# open_cw_keyer_mk2_v30.net
KiCad netlist of a schematic drawn in EAGLE
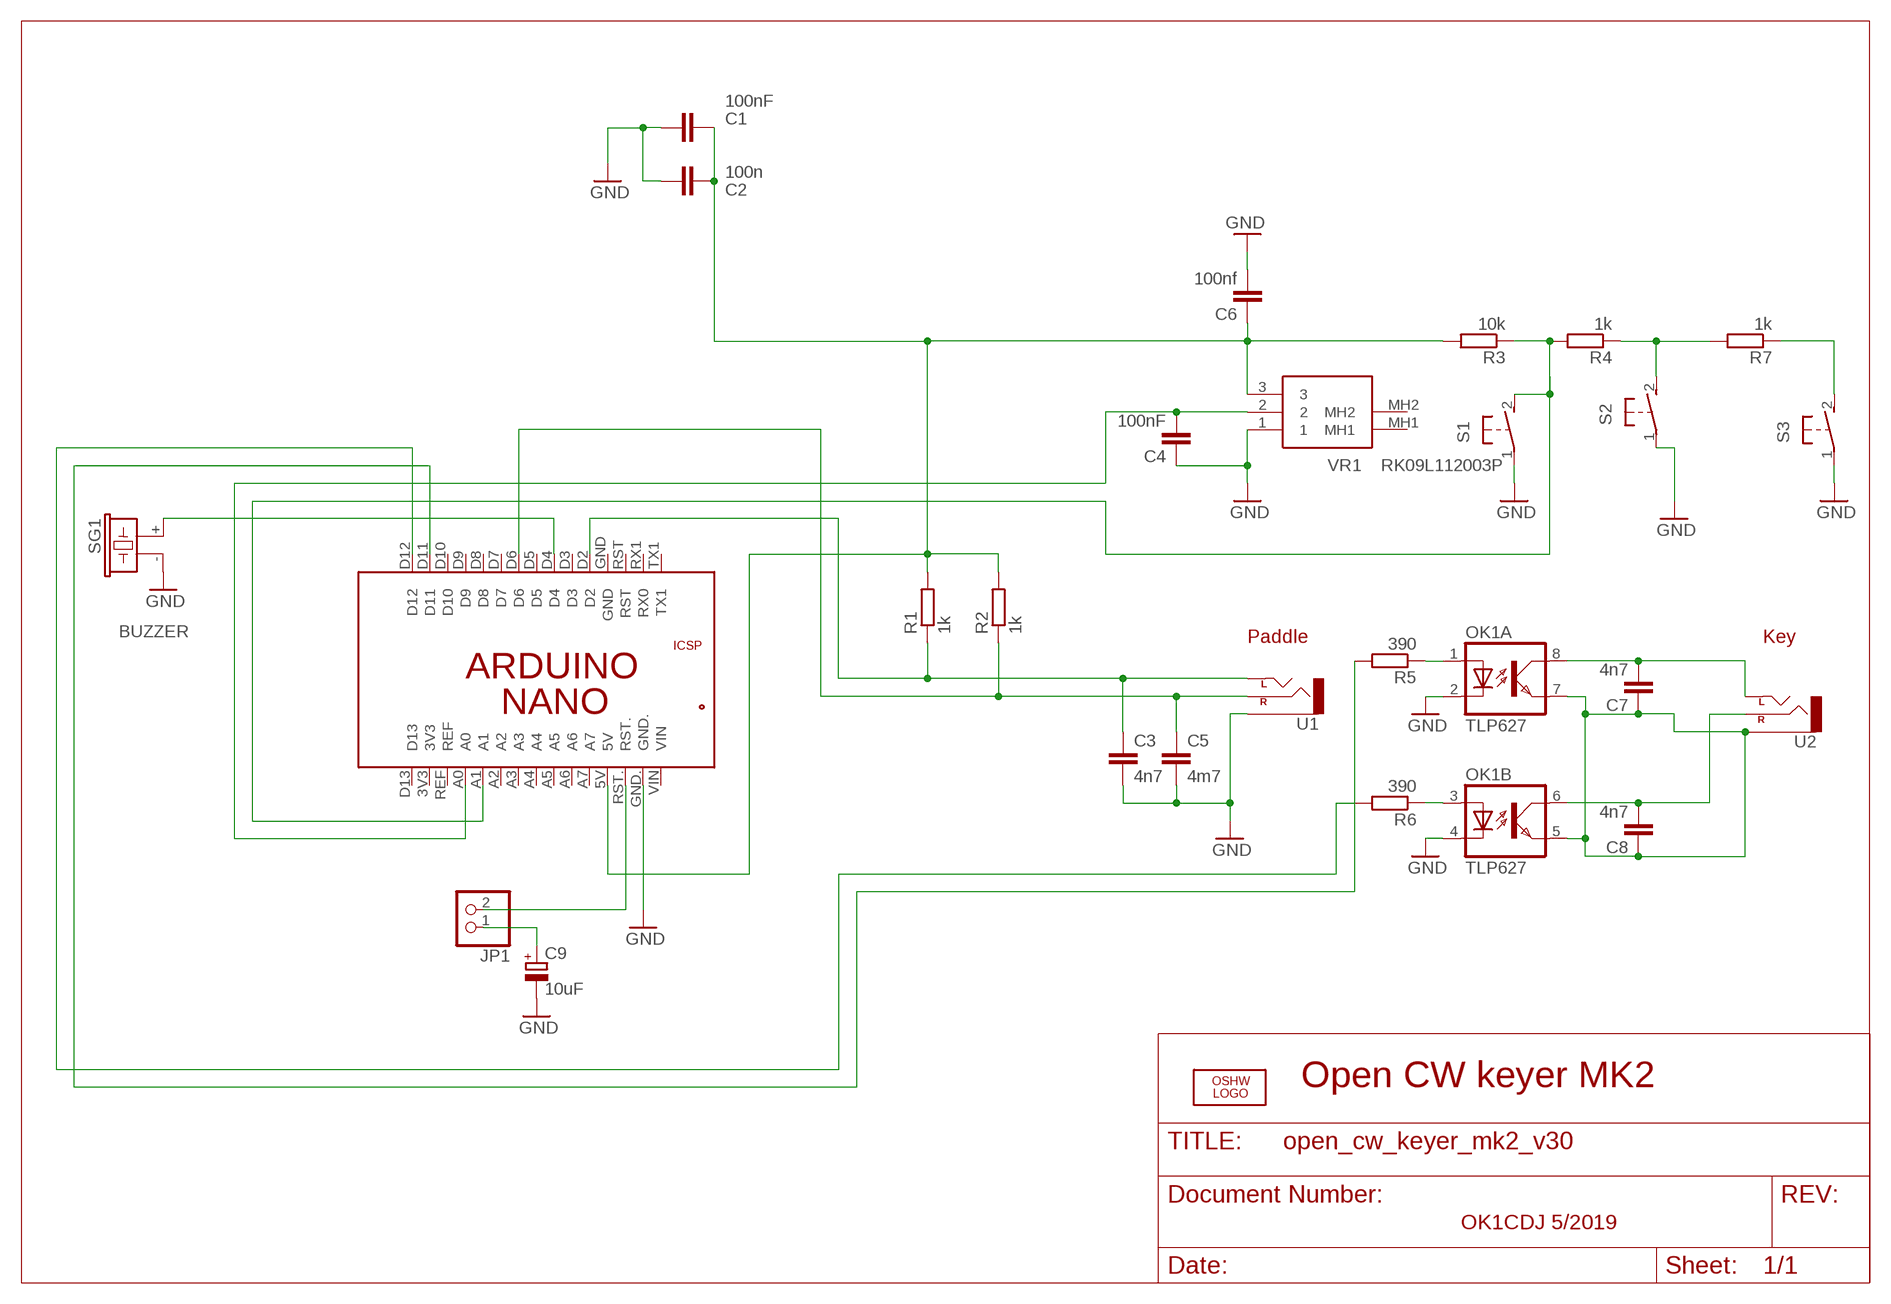
[diagram p0: schematic, sheet 1]

(export (version "E")
  (design (tool "Eeschema 10.0.6"))
  (components
    (comp (ref "C1")
      (value "100nF")
      (footprint "eagle-import:C0805")
      (libsource (lib "eagle-import") (part "C-EUC0805"))
    )
    (comp (ref "C2")
      (value "100n")
      (footprint "eagle-import:C0805")
      (libsource (lib "eagle-import") (part "C-EUC0805"))
    )
    (comp (ref "C3")
      (value "4n7")
      (footprint "eagle-import:C0805")
      (libsource (lib "eagle-import") (part "C-EUC0805"))
    )
    (comp (ref "C4")
      (value "100nF")
      (footprint "eagle-import:C0805")
      (libsource (lib "eagle-import") (part "C-EUC0805"))
    )
    (comp (ref "C5")
      (value "4m7")
      (footprint "eagle-import:C0805")
      (libsource (lib "eagle-import") (part "C-EUC0805"))
    )
    (comp (ref "C6")
      (value "100nf")
      (footprint "eagle-import:C0805")
      (libsource (lib "eagle-import") (part "C-EUC0805"))
    )
    (comp (ref "C7")
      (value "4n7")
      (footprint "eagle-import:C0805K")
      (libsource (lib "eagle-import") (part "C-EUC0805K"))
    )
    (comp (ref "C8")
      (value "4n7")
      (footprint "eagle-import:C0805K")
      (libsource (lib "eagle-import") (part "C-EUC0805K"))
    )
    (comp (ref "C9")
      (value "10uF")
      (footprint "eagle-import:B_3528-21R")
      (libsource (lib "eagle-import") (part "CPOL-EUB/3528-21R"))
    )
    (comp (ref "JP1")
      (value "PINHD-1X2/90")
      (footprint "eagle-import:1X02_90")
      (libsource (lib "eagle-import") (part "PINHD-1X2/90"))
    )
    (comp (ref "LOGO1")
      (value "OSHW_LOGO_FILLX0150-NT")
      (footprint "eagle-import:OSHW_FILLX150_NOTEXT")
      (libsource (lib "eagle-import") (part "OSHW_LOGO_FILLX0150-NT"))
    )
    (comp (ref "OK1")
      (value "TLP627")
      (footprint "eagle-import:DIL08")
      (fields (field (name "MF") "VISHAY/TELEFUNKEN") (field (name "MPN") "ILD621"))
      (libsource (lib "eagle-import") (part "ILD621"))
    )
    (comp (ref "PCB1")
      (value "ARDUINO_NANO")
      (footprint "eagle-import:ARDUINO_NANO")
      (libsource (lib "eagle-import") (part "ARDUINO_NANO"))
    )
    (comp (ref "R1")
      (value "1k")
      (footprint "eagle-import:M0805")
      (libsource (lib "eagle-import") (part "R-EU_M0805"))
    )
    (comp (ref "R2")
      (value "1k")
      (footprint "eagle-import:M0805")
      (libsource (lib "eagle-import") (part "R-EU_M0805"))
    )
    (comp (ref "R3")
      (value "10k")
      (footprint "eagle-import:M0805")
      (libsource (lib "eagle-import") (part "resistor_R-EU_M0805"))
    )
    (comp (ref "R4")
      (value "1k")
      (footprint "eagle-import:M0805")
      (libsource (lib "eagle-import") (part "resistor_R-EU_M0805"))
    )
    (comp (ref "R5")
      (value "390")
      (footprint "eagle-import:M0805")
      (libsource (lib "eagle-import") (part "resistor_R-EU_M0805"))
    )
    (comp (ref "R6")
      (value "390")
      (footprint "eagle-import:M0805")
      (libsource (lib "eagle-import") (part "resistor_R-EU_M0805"))
    )
    (comp (ref "R7")
      (value "1k")
      (footprint "eagle-import:M0805")
      (libsource (lib "eagle-import") (part "resistor_R-EU_M0805"))
    )
    (comp (ref "S1")
      (value "31-XX")
      (footprint "eagle-import:B3F-31XX")
      (fields (field (name "MPN") "B3F-3100"))
      (libsource (lib "eagle-import") (part "31-XX"))
    )
    (comp (ref "S2")
      (value "31-XX")
      (footprint "eagle-import:B3F-31XX")
      (fields (field (name "MPN") "B3F-3100"))
      (libsource (lib "eagle-import") (part "31-XX"))
    )
    (comp (ref "S3")
      (value "31-XX")
      (footprint "eagle-import:B3F-31XX")
      (fields (field (name "MPN") "B3F-3100"))
      (libsource (lib "eagle-import") (part "31-XX"))
    )
    (comp (ref "SG1")
      (value "BUZZER")
      (footprint "eagle-import:F_CM12P")
      (libsource (lib "eagle-import") (part "F/CM12P"))
    )
    (comp (ref "U1")
      (value "AUDIO-JACKPTH")
      (footprint "eagle-import:AUDIO-JACK")
      (libsource (lib "eagle-import") (part "AUDIO-JACKPTH"))
    )
    (comp (ref "U2")
      (value "AUDIO-JACKPTH")
      (footprint "eagle-import:AUDIO-JACK")
      (libsource (lib "eagle-import") (part "AUDIO-JACKPTH"))
    )
    (comp (ref "VR1")
      (value "RK09L112003P")
      (footprint "eagle-import:RK09L112003P")
      (fields (field (name "MOUSER_PART_NUMBER") "688-RK09L112003P"))
      (libsource (lib "eagle-import") (part "RK09L112003P"))
    )
  )
  (nets
    (net (code "1") (name "GND") (class "Default")
      (node (ref "C1") (pin "2") (pinfunction "2_2") (pintype "passive"))
      (node (ref "C2") (pin "2") (pinfunction "2_2") (pintype "passive"))
      (node (ref "C3") (pin "2") (pinfunction "2_2") (pintype "passive"))
      (node (ref "C4") (pin "1") (pinfunction "1_1") (pintype "passive"))
      (node (ref "C5") (pin "2") (pinfunction "2_2") (pintype "passive"))
      (node (ref "C6") (pin "2") (pinfunction "2_2") (pintype "passive"))
      (node (ref "C9") (pin "-") (pinfunction "-_-") (pintype "passive"))
      (node (ref "OK1") (pin "2") (pinfunction "C_2") (pintype "passive"))
      (node (ref "OK1") (pin "4") (pinfunction "C_4") (pintype "passive"))
      (node (ref "PCB1") (pin "GND.") (pinfunction "GND._GND.") (pintype "bidirectional"))
      (node (ref "S1") (pin "1") (pinfunction "P_1") (pintype "passive"))
      (node (ref "S2") (pin "1") (pinfunction "P_1") (pintype "passive"))
      (node (ref "S3") (pin "1") (pinfunction "P_1") (pintype "passive"))
      (node (ref "SG1") (pin "-") (pinfunction "2_-") (pintype "passive"))
      (node (ref "U1") (pin "SLEEVE") (pinfunction "SLEEVE_SLEEVE") (pintype "bidirectional"))
      (node (ref "VR1") (pin "1") (pinfunction "1_1") (pintype "bidirectional"))
    )
    (net (code "2") (name "Net-(C1-Pad1)") (class "Default")
      (node (ref "C1") (pin "1") (pinfunction "1_1") (pintype "passive"))
      (node (ref "C2") (pin "1") (pinfunction "1_1") (pintype "passive"))
      (node (ref "C6") (pin "1") (pinfunction "1_1") (pintype "passive"))
      (node (ref "PCB1") (pin "5V") (pinfunction "5V_5V") (pintype "bidirectional"))
      (node (ref "R1") (pin "2") (pinfunction "2_2") (pintype "passive"))
      (node (ref "R2") (pin "2") (pinfunction "2_2") (pintype "passive"))
      (node (ref "R3") (pin "2") (pinfunction "2_2") (pintype "passive"))
      (node (ref "VR1") (pin "3") (pinfunction "3_3") (pintype "bidirectional"))
    )
    (net (code "3") (name "Net-(C4-Pad2)") (class "Default")
      (node (ref "C4") (pin "2") (pinfunction "2_2") (pintype "passive"))
      (node (ref "PCB1") (pin "A0") (pinfunction "A0_A0") (pintype "bidirectional"))
      (node (ref "VR1") (pin "2") (pinfunction "2_2") (pintype "bidirectional"))
    )
    (net (code "4") (name "Net-(C9-Pad+)") (class "Default")
      (node (ref "C9") (pin "+") (pinfunction "+_+") (pintype "passive"))
      (node (ref "JP1") (pin "1") (pinfunction "1_1") (pintype "passive"))
    )
    (net (code "5") (name "Net-(JP1-Pad2)") (class "Default")
      (node (ref "JP1") (pin "2") (pinfunction "2_2") (pintype "passive"))
      (node (ref "PCB1") (pin "RST.") (pinfunction "RST._RST.") (pintype "bidirectional"))
    )
    (net (code "6") (name "Net-(OK1A-A)") (class "Default")
      (node (ref "OK1") (pin "1") (pinfunction "A_1") (pintype "passive"))
      (node (ref "R5") (pin "1") (pinfunction "1_1") (pintype "passive"))
    )
    (net (code "7") (name "Net-(OK1A-COL)") (class "Default")
      (node (ref "C7") (pin "2") (pinfunction "2_2") (pintype "passive"))
      (node (ref "OK1") (pin "8") (pinfunction "COL_8") (pintype "passive"))
      (node (ref "U2") (pin "TIP") (pinfunction "LEFT_TIP") (pintype "bidirectional"))
    )
    (net (code "8") (name "Net-(OK1A-EMIT)") (class "Default")
      (node (ref "C7") (pin "1") (pinfunction "1_1") (pintype "passive"))
      (node (ref "C8") (pin "1") (pinfunction "1_1") (pintype "passive"))
      (node (ref "OK1") (pin "5") (pinfunction "EMIT_5") (pintype "passive"))
      (node (ref "OK1") (pin "7") (pinfunction "EMIT_7") (pintype "passive"))
      (node (ref "U2") (pin "SLEEVE") (pinfunction "SLEEVE_SLEEVE") (pintype "bidirectional"))
    )
    (net (code "9") (name "Net-(OK1B-A)") (class "Default")
      (node (ref "OK1") (pin "3") (pinfunction "A_3") (pintype "passive"))
      (node (ref "R6") (pin "1") (pinfunction "1_1") (pintype "passive"))
    )
    (net (code "10") (name "Net-(OK1B-COL)") (class "Default")
      (node (ref "C8") (pin "2") (pinfunction "2_2") (pintype "passive"))
      (node (ref "OK1") (pin "6") (pinfunction "COL_6") (pintype "passive"))
      (node (ref "U2") (pin "RING") (pinfunction "RIGHT_RING") (pintype "bidirectional"))
    )
    (net (code "11") (name "Net-(PCB1-PadD11)") (class "Default")
      (node (ref "PCB1") (pin "D11") (pinfunction "D11_D11") (pintype "bidirectional"))
      (node (ref "R5") (pin "2") (pinfunction "2_2") (pintype "passive"))
    )
    (net (code "12") (name "Net-(PCB1-PadD12)") (class "Default")
      (node (ref "PCB1") (pin "D12") (pinfunction "D12_D12") (pintype "bidirectional"))
      (node (ref "R6") (pin "2") (pinfunction "2_2") (pintype "passive"))
    )
    (net (code "13") (name "Net-(S1-S)") (class "Default")
      (node (ref "PCB1") (pin "A1") (pinfunction "A1_A1") (pintype "bidirectional"))
      (node (ref "R3") (pin "1") (pinfunction "1_1") (pintype "passive"))
      (node (ref "R4") (pin "2") (pinfunction "2_2") (pintype "passive"))
      (node (ref "S1") (pin "2") (pinfunction "S_2") (pintype "passive"))
    )
    (net (code "14") (name "Net-(S2-S)") (class "Default")
      (node (ref "R4") (pin "1") (pinfunction "1_1") (pintype "passive"))
      (node (ref "R7") (pin "2") (pinfunction "2_2") (pintype "passive"))
      (node (ref "S2") (pin "2") (pinfunction "S_2") (pintype "passive"))
    )
    (net (code "15") (name "Net-(S3-S)") (class "Default")
      (node (ref "R7") (pin "1") (pinfunction "1_1") (pintype "passive"))
      (node (ref "S3") (pin "2") (pinfunction "S_2") (pintype "passive"))
    )
    (net (code "16") (name "Net-(SG1-1)") (class "Default")
      (node (ref "PCB1") (pin "D4") (pinfunction "D4_D4") (pintype "bidirectional"))
      (node (ref "SG1") (pin "+") (pinfunction "1_+") (pintype "passive"))
    )
    (net (code "17") (name "Net-(U1-LEFT)") (class "Default")
      (node (ref "C3") (pin "1") (pinfunction "1_1") (pintype "passive"))
      (node (ref "PCB1") (pin "D2") (pinfunction "D2_D2") (pintype "bidirectional"))
      (node (ref "R1") (pin "1") (pinfunction "1_1") (pintype "passive"))
      (node (ref "U1") (pin "TIP") (pinfunction "LEFT_TIP") (pintype "bidirectional"))
    )
    (net (code "18") (name "Net-(U1-RIGHT)") (class "Default")
      (node (ref "C5") (pin "1") (pinfunction "1_1") (pintype "passive"))
      (node (ref "PCB1") (pin "D6") (pinfunction "D6_D6") (pintype "bidirectional"))
      (node (ref "R2") (pin "1") (pinfunction "1_1") (pintype "passive"))
      (node (ref "U1") (pin "RING") (pinfunction "RIGHT_RING") (pintype "bidirectional"))
    )
    (net (code "19") (name "unconnected-(PCB1-Pad3V3)") (class "Default")
      (node (ref "PCB1") (pin "3V3") (pinfunction "3V3_3V3") (pintype "bidirectional"))
    )
    (net (code "20") (name "unconnected-(PCB1-Pad5V.)") (class "Default")
      (node (ref "PCB1") (pin "5V.") (pinfunction "5V._5V.") (pintype "bidirectional"))
    )
    (net (code "21") (name "unconnected-(PCB1-PadA2)") (class "Default")
      (node (ref "PCB1") (pin "A2") (pinfunction "A2_A2") (pintype "bidirectional"))
    )
    (net (code "22") (name "unconnected-(PCB1-PadA3)") (class "Default")
      (node (ref "PCB1") (pin "A3") (pinfunction "A3_A3") (pintype "bidirectional"))
    )
    (net (code "23") (name "unconnected-(PCB1-PadA4)") (class "Default")
      (node (ref "PCB1") (pin "A4") (pinfunction "A4_A4") (pintype "bidirectional"))
    )
    (net (code "24") (name "unconnected-(PCB1-PadA5)") (class "Default")
      (node (ref "PCB1") (pin "A5") (pinfunction "A5_A5") (pintype "bidirectional"))
    )
    (net (code "25") (name "unconnected-(PCB1-PadA6)") (class "Default")
      (node (ref "PCB1") (pin "A6") (pinfunction "A6_A6") (pintype "bidirectional"))
    )
    (net (code "26") (name "unconnected-(PCB1-PadA7)") (class "Default")
      (node (ref "PCB1") (pin "A7") (pinfunction "A7_A7") (pintype "bidirectional"))
    )
    (net (code "27") (name "unconnected-(PCB1-PadD3)") (class "Default")
      (node (ref "PCB1") (pin "D3") (pinfunction "D3_D3") (pintype "bidirectional"))
    )
    (net (code "28") (name "unconnected-(PCB1-PadD5)") (class "Default")
      (node (ref "PCB1") (pin "D5") (pinfunction "D5_D5") (pintype "bidirectional"))
    )
    (net (code "29") (name "unconnected-(PCB1-PadD7)") (class "Default")
      (node (ref "PCB1") (pin "D7") (pinfunction "D7_D7") (pintype "bidirectional"))
    )
    (net (code "30") (name "unconnected-(PCB1-PadD8)") (class "Default")
      (node (ref "PCB1") (pin "D8") (pinfunction "D8_D8") (pintype "bidirectional"))
    )
    (net (code "31") (name "unconnected-(PCB1-PadD9)") (class "Default")
      (node (ref "PCB1") (pin "D9") (pinfunction "D9_D9") (pintype "bidirectional"))
    )
    (net (code "32") (name "unconnected-(PCB1-PadD10)") (class "Default")
      (node (ref "PCB1") (pin "D10") (pinfunction "D10_D10") (pintype "bidirectional"))
    )
    (net (code "33") (name "unconnected-(PCB1-PadD13)") (class "Default")
      (node (ref "PCB1") (pin "D13") (pinfunction "D13_D13") (pintype "bidirectional"))
    )
    (net (code "34") (name "unconnected-(PCB1-PadGND)") (class "Default")
      (node (ref "PCB1") (pin "GND") (pinfunction "GND_GND") (pintype "bidirectional"))
    )
    (net (code "35") (name "unconnected-(PCB1-PadGND_)") (class "Default")
      (node (ref "PCB1") (pin "GND_") (pinfunction "GND__GND_") (pintype "bidirectional"))
    )
    (net (code "36") (name "unconnected-(PCB1-PadMISO)") (class "Default")
      (node (ref "PCB1") (pin "MISO") (pinfunction "MISO_MISO") (pintype "bidirectional"))
    )
    (net (code "37") (name "unconnected-(PCB1-PadMOSI)") (class "Default")
      (node (ref "PCB1") (pin "MOSI") (pinfunction "MOSI_MOSI") (pintype "bidirectional"))
    )
    (net (code "38") (name "unconnected-(PCB1-PadREF)") (class "Default")
      (node (ref "PCB1") (pin "REF") (pinfunction "REF_REF") (pintype "bidirectional"))
    )
    (net (code "39") (name "unconnected-(PCB1-PadRESET..)") (class "Default")
      (node (ref "PCB1") (pin "RESET..") (pinfunction "RESET.._RESET..") (pintype "bidirectional"))
    )
    (net (code "40") (name "unconnected-(PCB1-PadRST)") (class "Default")
      (node (ref "PCB1") (pin "RST") (pinfunction "RST_RST") (pintype "bidirectional"))
    )
    (net (code "41") (name "unconnected-(PCB1-PadSCK)") (class "Default")
      (node (ref "PCB1") (pin "SCK") (pinfunction "SCK_SCK") (pintype "bidirectional"))
    )
    (net (code "42") (name "unconnected-(PCB1-PadTX1)") (class "Default")
      (node (ref "PCB1") (pin "TX1") (pinfunction "TX1_TX1") (pintype "bidirectional"))
    )
    (net (code "43") (name "unconnected-(PCB1-PadVIN)") (class "Default")
      (node (ref "PCB1") (pin "VIN") (pinfunction "VIN_VIN") (pintype "bidirectional"))
    )
    (net (code "44") (name "unconnected-(PCB1-RX0-PadRX1)") (class "Default")
      (node (ref "PCB1") (pin "RX1") (pinfunction "RX0_RX1") (pintype "bidirectional"))
    )
    (net (code "45") (name "unconnected-(VR1-PadMH1)") (class "Default")
      (node (ref "VR1") (pin "MH1") (pinfunction "MH1_MH1") (pintype "bidirectional"))
    )
    (net (code "46") (name "unconnected-(VR1-PadMH2)") (class "Default")
      (node (ref "VR1") (pin "MH2") (pinfunction "MH2_MH2") (pintype "bidirectional"))
    )
  )
)
